# photonNixieTop.net
KiCad netlist of a schematic drawn in EAGLE
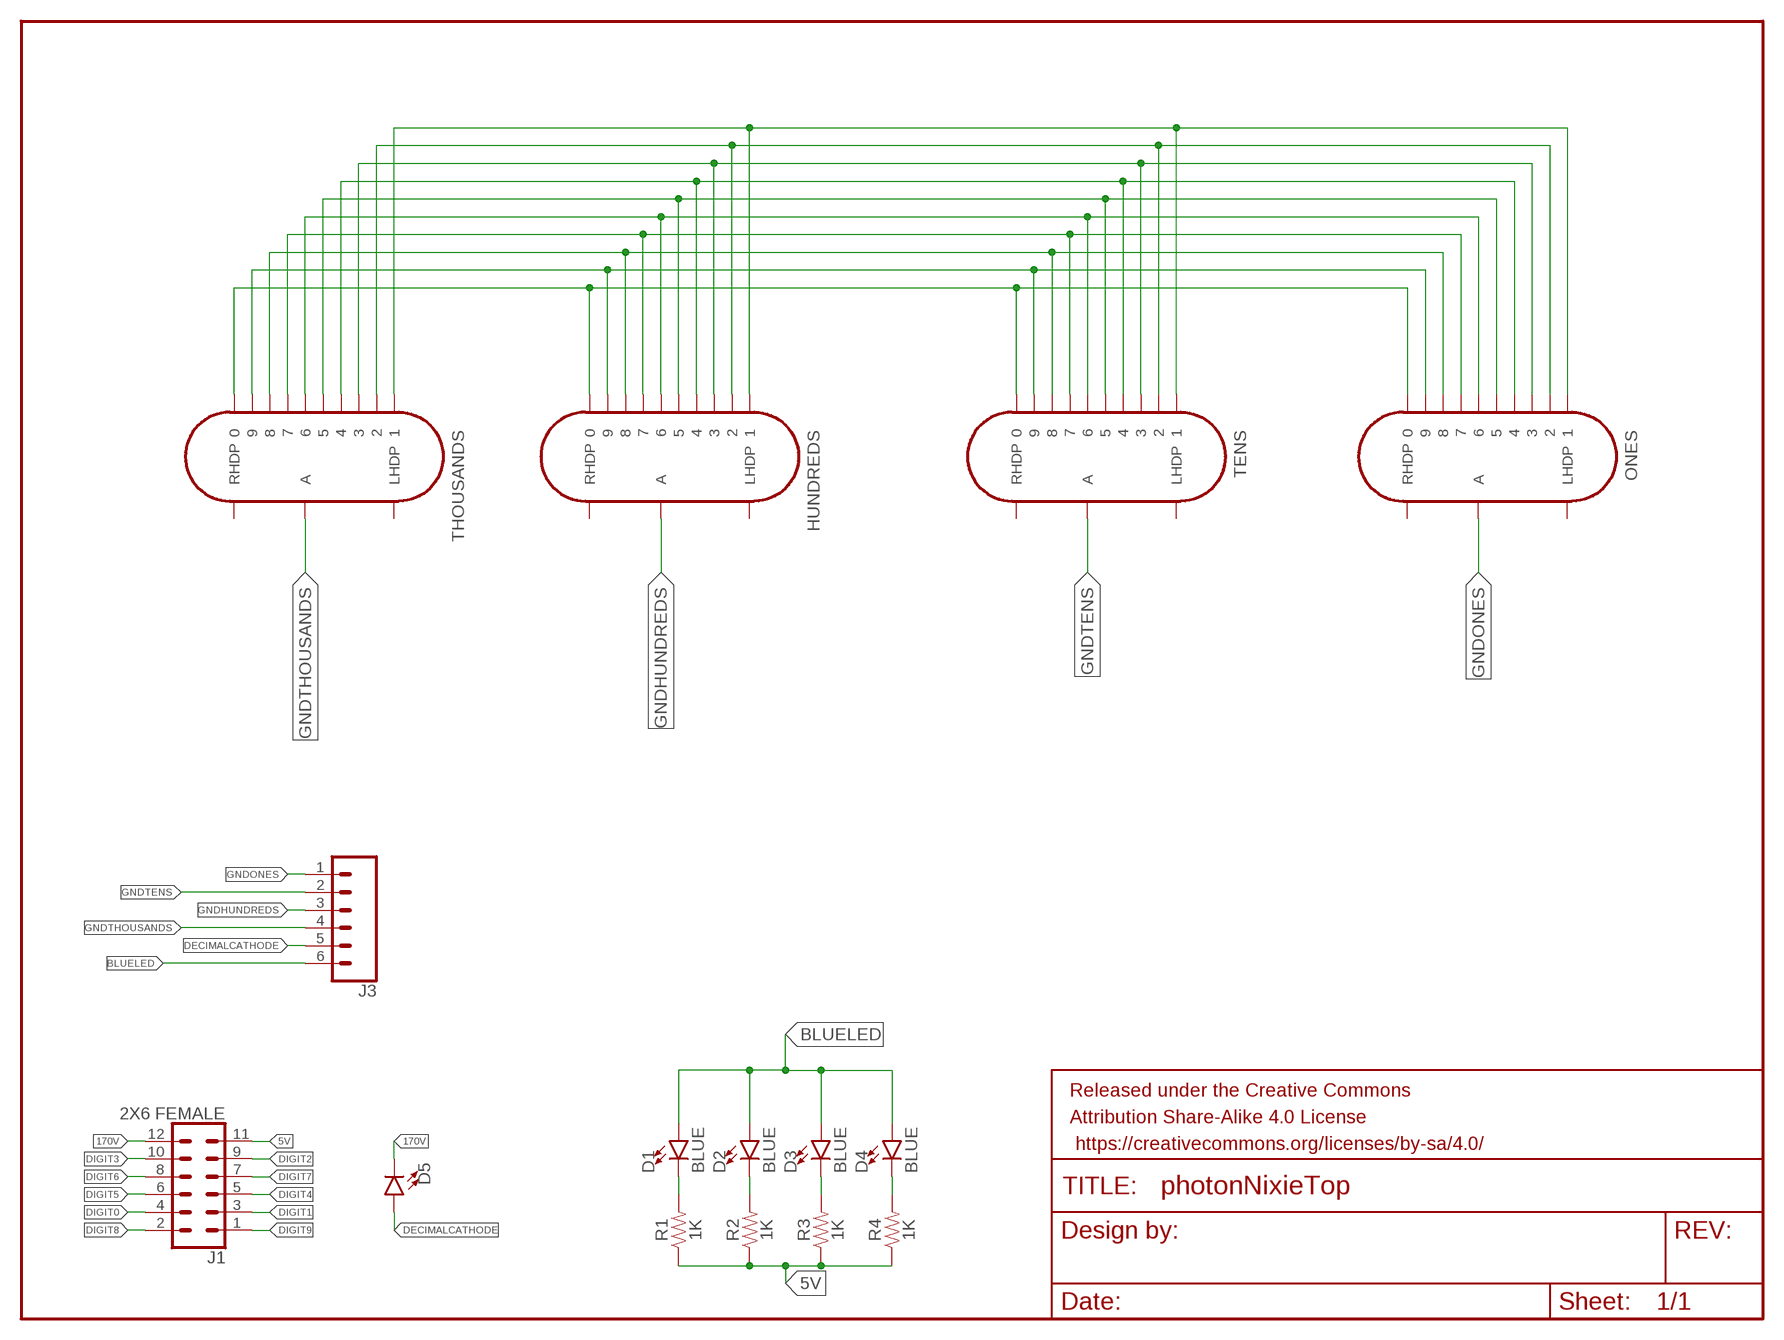
[diagram p0: schematic, sheet 1]

(export (version "E")
  (design (tool "Eeschema 10.0.6"))
  (components
    (comp (ref "D1")
      (value "BLUE")
      (footprint "eagle-import:LED-1206")
      (libsource (lib "eagle-import") (part "LED-BLUE1206"))
    )
    (comp (ref "D2")
      (value "BLUE")
      (footprint "eagle-import:LED-1206")
      (libsource (lib "eagle-import") (part "LED-BLUE1206"))
    )
    (comp (ref "D3")
      (value "BLUE")
      (footprint "eagle-import:LED-1206")
      (libsource (lib "eagle-import") (part "LED-BLUE1206"))
    )
    (comp (ref "D4")
      (value "BLUE")
      (footprint "eagle-import:LED-1206")
      (libsource (lib "eagle-import") (part "LED-BLUE1206"))
    )
    (comp (ref "D5")
      (value "LED5MM")
      (footprint "eagle-import:LED_5MM")
      (libsource (lib "eagle-import") (part "LED5MM"))
    )
    (comp (ref "FRAME1")
      (value "FRAME-LETTER")
      (footprint "eagle-import:CREATIVE_COMMONS")
      (libsource (lib "eagle-import") (part "FRAME-LETTER"))
    )
    (comp (ref "HUNDREDS")
      (value "IN-14")
      (footprint "eagle-import:IN-14")
      (libsource (lib "eagle-import") (part "IN-14"))
    )
    (comp (ref "J1")
      (value "2X6 FEMALE")
      (footprint "eagle-import:2X6")
      (libsource (lib "eagle-import") (part "CONN_06X2PTH_FEMALE"))
    )
    (comp (ref "J3")
      (value "CONN_06SILK_FEMALE_PTH")
      (footprint "eagle-import:1X06")
      (libsource (lib "eagle-import") (part "CONN_06SILK_FEMALE_PTH"))
    )
    (comp (ref "ONES")
      (value "IN-14")
      (footprint "eagle-import:IN-14")
      (libsource (lib "eagle-import") (part "IN-14"))
    )
    (comp (ref "R1")
      (value "1K")
      (footprint "eagle-import:0805")
      (libsource (lib "eagle-import") (part "0.3OHM-0805-1/8W-1%"))
    )
    (comp (ref "R2")
      (value "1K")
      (footprint "eagle-import:0805")
      (libsource (lib "eagle-import") (part "0.3OHM-0805-1/8W-1%"))
    )
    (comp (ref "R3")
      (value "1K")
      (footprint "eagle-import:0805")
      (libsource (lib "eagle-import") (part "0.3OHM-0805-1/8W-1%"))
    )
    (comp (ref "R4")
      (value "1K")
      (footprint "eagle-import:0805")
      (libsource (lib "eagle-import") (part "0.3OHM-0805-1/8W-1%"))
    )
    (comp (ref "TENS")
      (value "IN-14")
      (footprint "eagle-import:IN-14")
      (libsource (lib "eagle-import") (part "IN-14"))
    )
    (comp (ref "THOUSANDS")
      (value "IN-14")
      (footprint "eagle-import:IN-14")
      (libsource (lib "eagle-import") (part "IN-14"))
    )
  )
  (nets
    (net (code "1") (name "5V") (class "Default")
      (node (ref "J1") (pin "11") (pinfunction "11_11") (pintype "passive"))
      (node (ref "R1") (pin "1") (pinfunction "1_1") (pintype "passive"))
      (node (ref "R2") (pin "1") (pinfunction "1_1") (pintype "passive"))
      (node (ref "R3") (pin "1") (pinfunction "1_1") (pintype "passive"))
      (node (ref "R4") (pin "1") (pinfunction "1_1") (pintype "passive"))
    )
    (net (code "2") (name "170V") (class "Default")
      (node (ref "D5") (pin "K") (pinfunction "C_K") (pintype "passive"))
      (node (ref "J1") (pin "12") (pinfunction "12_12") (pintype "passive"))
    )
    (net (code "3") (name "BLUELED") (class "Default")
      (node (ref "D1") (pin "A") (pinfunction "A_A") (pintype "passive"))
      (node (ref "D2") (pin "A") (pinfunction "A_A") (pintype "passive"))
      (node (ref "D3") (pin "A") (pinfunction "A_A") (pintype "passive"))
      (node (ref "D4") (pin "A") (pinfunction "A_A") (pintype "passive"))
      (node (ref "J3") (pin "6") (pinfunction "6_6") (pintype "passive"))
    )
    (net (code "4") (name "DECIMALCATHODE") (class "Default")
      (node (ref "D5") (pin "A") (pinfunction "A_A") (pintype "passive"))
      (node (ref "J3") (pin "5") (pinfunction "5_5") (pintype "passive"))
    )
    (net (code "5") (name "DIGIT0") (class "Default")
      (node (ref "HUNDREDS") (pin "0") (pinfunction "0_0") (pintype "bidirectional"))
      (node (ref "J1") (pin "4") (pinfunction "4_4") (pintype "passive"))
      (node (ref "ONES") (pin "0") (pinfunction "0_0") (pintype "bidirectional"))
      (node (ref "TENS") (pin "0") (pinfunction "0_0") (pintype "bidirectional"))
      (node (ref "THOUSANDS") (pin "0") (pinfunction "0_0") (pintype "bidirectional"))
    )
    (net (code "6") (name "DIGIT1") (class "Default")
      (node (ref "HUNDREDS") (pin "1") (pinfunction "1_1") (pintype "bidirectional"))
      (node (ref "J1") (pin "3") (pinfunction "3_3") (pintype "passive"))
      (node (ref "ONES") (pin "1") (pinfunction "1_1") (pintype "bidirectional"))
      (node (ref "TENS") (pin "1") (pinfunction "1_1") (pintype "bidirectional"))
      (node (ref "THOUSANDS") (pin "1") (pinfunction "1_1") (pintype "bidirectional"))
    )
    (net (code "7") (name "DIGIT2") (class "Default")
      (node (ref "HUNDREDS") (pin "2") (pinfunction "2_2") (pintype "bidirectional"))
      (node (ref "J1") (pin "9") (pinfunction "9_9") (pintype "passive"))
      (node (ref "ONES") (pin "2") (pinfunction "2_2") (pintype "bidirectional"))
      (node (ref "TENS") (pin "2") (pinfunction "2_2") (pintype "bidirectional"))
      (node (ref "THOUSANDS") (pin "2") (pinfunction "2_2") (pintype "bidirectional"))
    )
    (net (code "8") (name "DIGIT3") (class "Default")
      (node (ref "HUNDREDS") (pin "3") (pinfunction "3_3") (pintype "bidirectional"))
      (node (ref "J1") (pin "10") (pinfunction "10_10") (pintype "passive"))
      (node (ref "ONES") (pin "3") (pinfunction "3_3") (pintype "bidirectional"))
      (node (ref "TENS") (pin "3") (pinfunction "3_3") (pintype "bidirectional"))
      (node (ref "THOUSANDS") (pin "3") (pinfunction "3_3") (pintype "bidirectional"))
    )
    (net (code "9") (name "DIGIT4") (class "Default")
      (node (ref "HUNDREDS") (pin "4") (pinfunction "4_4") (pintype "bidirectional"))
      (node (ref "J1") (pin "5") (pinfunction "5_5") (pintype "passive"))
      (node (ref "ONES") (pin "4") (pinfunction "4_4") (pintype "bidirectional"))
      (node (ref "TENS") (pin "4") (pinfunction "4_4") (pintype "bidirectional"))
      (node (ref "THOUSANDS") (pin "4") (pinfunction "4_4") (pintype "bidirectional"))
    )
    (net (code "10") (name "DIGIT5") (class "Default")
      (node (ref "HUNDREDS") (pin "5") (pinfunction "5_5") (pintype "bidirectional"))
      (node (ref "J1") (pin "6") (pinfunction "6_6") (pintype "passive"))
      (node (ref "ONES") (pin "5") (pinfunction "5_5") (pintype "bidirectional"))
      (node (ref "TENS") (pin "5") (pinfunction "5_5") (pintype "bidirectional"))
      (node (ref "THOUSANDS") (pin "5") (pinfunction "5_5") (pintype "bidirectional"))
    )
    (net (code "11") (name "DIGIT6") (class "Default")
      (node (ref "HUNDREDS") (pin "6") (pinfunction "6_6") (pintype "bidirectional"))
      (node (ref "J1") (pin "8") (pinfunction "8_8") (pintype "passive"))
      (node (ref "ONES") (pin "6") (pinfunction "6_6") (pintype "bidirectional"))
      (node (ref "TENS") (pin "6") (pinfunction "6_6") (pintype "bidirectional"))
      (node (ref "THOUSANDS") (pin "6") (pinfunction "6_6") (pintype "bidirectional"))
    )
    (net (code "12") (name "DIGIT7") (class "Default")
      (node (ref "HUNDREDS") (pin "7") (pinfunction "7_7") (pintype "bidirectional"))
      (node (ref "J1") (pin "7") (pinfunction "7_7") (pintype "passive"))
      (node (ref "ONES") (pin "7") (pinfunction "7_7") (pintype "bidirectional"))
      (node (ref "TENS") (pin "7") (pinfunction "7_7") (pintype "bidirectional"))
      (node (ref "THOUSANDS") (pin "7") (pinfunction "7_7") (pintype "bidirectional"))
    )
    (net (code "13") (name "DIGIT8") (class "Default")
      (node (ref "HUNDREDS") (pin "8") (pinfunction "8_8") (pintype "bidirectional"))
      (node (ref "J1") (pin "2") (pinfunction "2_2") (pintype "passive"))
      (node (ref "ONES") (pin "8") (pinfunction "8_8") (pintype "bidirectional"))
      (node (ref "TENS") (pin "8") (pinfunction "8_8") (pintype "bidirectional"))
      (node (ref "THOUSANDS") (pin "8") (pinfunction "8_8") (pintype "bidirectional"))
    )
    (net (code "14") (name "DIGIT9") (class "Default")
      (node (ref "HUNDREDS") (pin "9") (pinfunction "9_9") (pintype "bidirectional"))
      (node (ref "J1") (pin "1") (pinfunction "1_1") (pintype "passive"))
      (node (ref "ONES") (pin "9") (pinfunction "9_9") (pintype "bidirectional"))
      (node (ref "TENS") (pin "9") (pinfunction "9_9") (pintype "bidirectional"))
      (node (ref "THOUSANDS") (pin "9") (pinfunction "9_9") (pintype "bidirectional"))
    )
    (net (code "15") (name "GNDHUNDREDS") (class "Default")
      (node (ref "HUNDREDS") (pin "A") (pinfunction "A_A") (pintype "bidirectional"))
      (node (ref "J3") (pin "3") (pinfunction "3_3") (pintype "passive"))
    )
    (net (code "16") (name "GNDONES") (class "Default")
      (node (ref "J3") (pin "1") (pinfunction "1_1") (pintype "passive"))
      (node (ref "ONES") (pin "A") (pinfunction "A_A") (pintype "bidirectional"))
    )
    (net (code "17") (name "GNDTENS") (class "Default")
      (node (ref "J3") (pin "2") (pinfunction "2_2") (pintype "passive"))
      (node (ref "TENS") (pin "A") (pinfunction "A_A") (pintype "bidirectional"))
    )
    (net (code "18") (name "GNDTHOUSANDS") (class "Default")
      (node (ref "J3") (pin "4") (pinfunction "4_4") (pintype "passive"))
      (node (ref "THOUSANDS") (pin "A") (pinfunction "A_A") (pintype "bidirectional"))
    )
    (net (code "19") (name "Net-(D1-PadC)") (class "Default")
      (node (ref "D1") (pin "C") (pinfunction "C_C") (pintype "passive"))
      (node (ref "R1") (pin "2") (pinfunction "2_2") (pintype "passive"))
    )
    (net (code "20") (name "Net-(D2-PadC)") (class "Default")
      (node (ref "D2") (pin "C") (pinfunction "C_C") (pintype "passive"))
      (node (ref "R2") (pin "2") (pinfunction "2_2") (pintype "passive"))
    )
    (net (code "21") (name "Net-(D3-PadC)") (class "Default")
      (node (ref "D3") (pin "C") (pinfunction "C_C") (pintype "passive"))
      (node (ref "R3") (pin "2") (pinfunction "2_2") (pintype "passive"))
    )
    (net (code "22") (name "Net-(D4-PadC)") (class "Default")
      (node (ref "D4") (pin "C") (pinfunction "C_C") (pintype "passive"))
      (node (ref "R4") (pin "2") (pinfunction "2_2") (pintype "passive"))
    )
    (net (code "23") (name "unconnected-(HUNDREDS-PadLHDP)") (class "Default")
      (node (ref "HUNDREDS") (pin "LHDP") (pinfunction "LHDP_LHDP") (pintype "bidirectional"))
    )
    (net (code "24") (name "unconnected-(HUNDREDS-PadRHDP)") (class "Default")
      (node (ref "HUNDREDS") (pin "RHDP") (pinfunction "RHDP_RHDP") (pintype "bidirectional"))
    )
    (net (code "25") (name "unconnected-(ONES-PadLHDP)") (class "Default")
      (node (ref "ONES") (pin "LHDP") (pinfunction "LHDP_LHDP") (pintype "bidirectional"))
    )
    (net (code "26") (name "unconnected-(ONES-PadRHDP)") (class "Default")
      (node (ref "ONES") (pin "RHDP") (pinfunction "RHDP_RHDP") (pintype "bidirectional"))
    )
    (net (code "27") (name "unconnected-(TENS-PadLHDP)") (class "Default")
      (node (ref "TENS") (pin "LHDP") (pinfunction "LHDP_LHDP") (pintype "bidirectional"))
    )
    (net (code "28") (name "unconnected-(TENS-PadRHDP)") (class "Default")
      (node (ref "TENS") (pin "RHDP") (pinfunction "RHDP_RHDP") (pintype "bidirectional"))
    )
    (net (code "29") (name "unconnected-(THOUSANDS-PadLHDP)") (class "Default")
      (node (ref "THOUSANDS") (pin "LHDP") (pinfunction "LHDP_LHDP") (pintype "bidirectional"))
    )
    (net (code "30") (name "unconnected-(THOUSANDS-PadRHDP)") (class "Default")
      (node (ref "THOUSANDS") (pin "RHDP") (pinfunction "RHDP_RHDP") (pintype "bidirectional"))
    )
  )
)
